# RFID.net
KiCad netlist of a schematic drawn in EAGLE
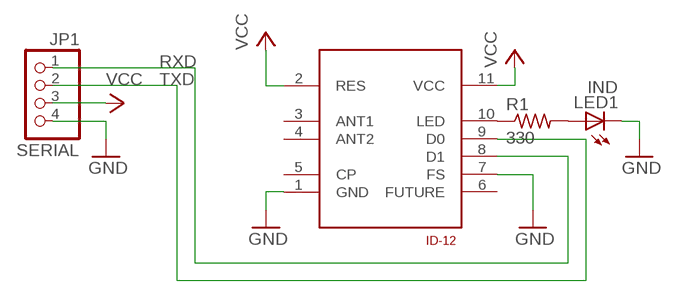
[diagram p0: schematic, sheet 1]

(export (version "E")
  (design (tool "Eeschema 10.0.6"))
  (components
    (comp (ref "JP1")
      (value "SERIAL")
      (footprint "eagle-import:1X04")
      (libsource (lib "eagle-import") (part "PINHD-1X4"))
    )
    (comp (ref "LED1")
      (value "IND")
      (footprint "eagle-import:LED3MM")
      (libsource (lib "eagle-import") (part "LED3MM"))
    )
    (comp (ref "R1")
      (value "330")
      (footprint "eagle-import:0207_10")
      (libsource (lib "eagle-import") (part "R-US_0207/10"))
    )
    (comp (ref "U$1")
      (value "ID-20")
      (footprint "eagle-import:ID-20")
      (libsource (lib "eagle-import") (part "ID-20"))
    )
  )
  (nets
    (net (code "1") (name "/RXD") (class "Default")
      (node (ref "JP1") (pin "1") (pinfunction "1_1") (pintype "passive"))
      (node (ref "U$1") (pin "8") (pinfunction "D1_8") (pintype "bidirectional"))
    )
    (net (code "2") (name "/TXD") (class "Default")
      (node (ref "JP1") (pin "2") (pinfunction "2_2") (pintype "passive"))
      (node (ref "U$1") (pin "9") (pinfunction "D0_9") (pintype "bidirectional"))
    )
    (net (code "3") (name "GND") (class "Default")
      (node (ref "JP1") (pin "4") (pinfunction "4_4") (pintype "passive"))
      (node (ref "LED1") (pin "K") (pinfunction "C_K") (pintype "passive"))
      (node (ref "U$1") (pin "1") (pinfunction "GND_1") (pintype "bidirectional"))
      (node (ref "U$1") (pin "7") (pinfunction "FS_7") (pintype "bidirectional"))
    )
    (net (code "4") (name "Net-(LED1-PadA)") (class "Default")
      (node (ref "LED1") (pin "A") (pinfunction "A_A") (pintype "passive"))
      (node (ref "R1") (pin "2") (pinfunction "2_2") (pintype "passive"))
    )
    (net (code "5") (name "Net-(U$1-LED)") (class "Default")
      (node (ref "R1") (pin "1") (pinfunction "1_1") (pintype "passive"))
      (node (ref "U$1") (pin "10") (pinfunction "LED_10") (pintype "bidirectional"))
    )
    (net (code "6") (name "VCC") (class "Default")
      (node (ref "JP1") (pin "3") (pinfunction "3_3") (pintype "passive"))
      (node (ref "U$1") (pin "11") (pinfunction "VCC_11") (pintype "bidirectional"))
      (node (ref "U$1") (pin "2") (pinfunction "RES_2") (pintype "bidirectional"))
    )
    (net (code "7") (name "unconnected-(U$1-ANT1-Pad3)") (class "Default")
      (node (ref "U$1") (pin "3") (pinfunction "ANT1_3") (pintype "bidirectional"))
    )
    (net (code "8") (name "unconnected-(U$1-ANT2-Pad4)") (class "Default")
      (node (ref "U$1") (pin "4") (pinfunction "ANT2_4") (pintype "bidirectional"))
    )
    (net (code "9") (name "unconnected-(U$1-CP-Pad5)") (class "Default")
      (node (ref "U$1") (pin "5") (pinfunction "CP_5") (pintype "bidirectional"))
    )
    (net (code "10") (name "unconnected-(U$1-FUTURE-Pad6)") (class "Default")
      (node (ref "U$1") (pin "6") (pinfunction "FUTURE_6") (pintype "bidirectional"))
    )
  )
)
